# Power.net
KiCad netlist of a schematic drawn in Altium Designer
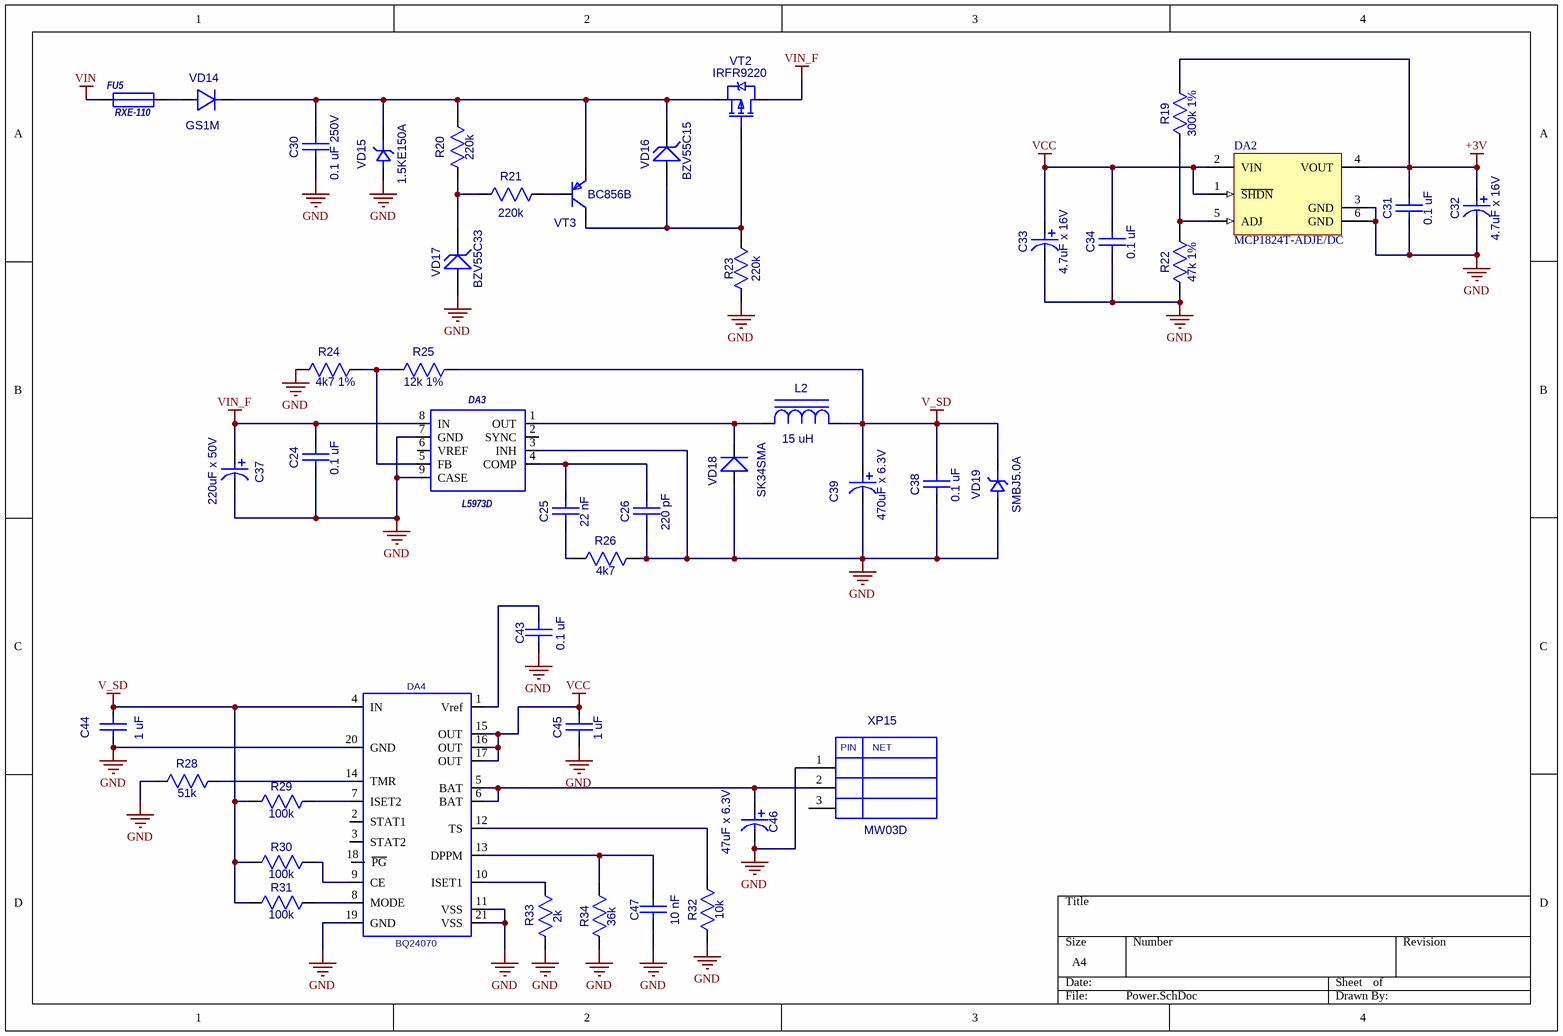
[diagram p0: Power.SchDoc]

(export (version "E")
  (design (tool "Eeschema 10.0.6"))
  (components
    (comp (ref "C24")
      (value "0.1 uF")
      (footprint "CC0603-3M")
      (description "CC0603")
      (libsource (lib "*") (part "CC0603"))
    )
    (comp (ref "C25")
      (value "22 nF")
      (footprint "CC0603-3M")
      (description "CC0603")
      (libsource (lib "*") (part "CC0603"))
    )
    (comp (ref "C26")
      (value "220 pF")
      (footprint "CC0603-3M")
      (description "CC0603")
      (libsource (lib "*") (part "CC0603"))
    )
    (comp (ref "C30")
      (value "0.1 uF 250V")
      (footprint "CC1206-MIDI")
      (description "CC1206")
      (libsource (lib "gprs_modem") (part "CC1206"))
    )
    (comp (ref "C31")
      (value "0.1 uF")
      (footprint "CC0603-3M")
      (description "CC0603")
      (libsource (lib "*") (part "CC0603"))
    )
    (comp (ref "C32")
      (value "4.7uF x 16V")
      (footprint "TAJ-A_M")
      (description "TAJ-A")
      (libsource (lib "*") (part "TAJ-A"))
    )
    (comp (ref "C33")
      (value "4.7uF x 16V")
      (footprint "TAJ-A_M")
      (description "TAJ-A")
      (libsource (lib "*") (part "TAJ-A"))
    )
    (comp (ref "C34")
      (value "0.1 uF")
      (footprint "CC0603-3M")
      (description "CC0603")
      (libsource (lib "*") (part "CC0603"))
    )
    (comp (ref "C37")
      (value "220uF x 50V")
      (footprint "CC16X10_CAP0.5(1)(Primary)")
      (description "CAP0.5(1)")
      (libsource (lib "gprs_modem") (part "CAP0.5(1)"))
    )
    (comp (ref "C38")
      (value "0.1 uF")
      (footprint "CC0603-3M")
      (description "CC0603")
      (libsource (lib "*") (part "CC0603"))
    )
    (comp (ref "C39")
      (value "470uF x 6.3V")
      (footprint "TAJ-D-1M")
      (description "TAJ-D")
      (libsource (lib "gprs_modem") (part "TAJ-D"))
    )
    (comp (ref "C43")
      (value "0.1 uF")
      (footprint "CC0603-3M")
      (description "CC0603")
      (libsource (lib "gprs_modem") (part "CC0603"))
    )
    (comp (ref "C44")
      (value "1 uF")
      (footprint "CC0603-3M")
      (description "CC0603")
      (libsource (lib "*") (part "CC0603"))
    )
    (comp (ref "C45")
      (value "1 uF")
      (footprint "CC0603-3M")
      (description "CC0603")
      (libsource (lib "*") (part "CC0603"))
    )
    (comp (ref "C46")
      (value "47uF x 6.3V")
      (footprint "TAJ-B-1M")
      (description "TAJ-B")
      (libsource (lib "*") (part "TAJ-B"))
    )
    (comp (ref "C47")
      (value "10 nF")
      (footprint "CC0603-3M")
      (description "CC0603")
      (libsource (lib "gprs_modem") (part "CC0603"))
    )
    (comp (ref "DA2")
      (value "MCP1824T-ADJE/DC")
      (footprint "SOT223-6")
      (fields (field (name "PUBLISHER") "Altium Limited"))
      (libsource (lib "gprs_modem") (part "MCP1824T-ADJE/DC"))
    )
    (comp (ref "DA3") (value "L5973D") (footprint "SO-8_EXP_PAD") (libsource (lib "*") (part "L5973D")))
    (comp (ref "DA4")
      (value "BQ24070")
      (footprint "P-PQFP-N20")
      (libsource (lib "gprs_modem") (part "BQ24070"))
    )
    (comp (ref "FU5") (value "RXE-110") (footprint "RXE-110") (libsource (lib "gprs_modem") (part "RXE-110")))
    (comp (ref "L2")
      (value "15 uH")
      (footprint "SDR0805")
      (description "SDR0805")
      (libsource (lib "*") (part "SDR0805"))
    )
    (comp (ref "R19")
      (value "300k 1%")
      (footprint "RC0603-3M")
      (description "RC0603")
      (libsource (lib "*") (part "RC0603"))
    )
    (comp (ref "R20")
      (value "220k")
      (footprint "RC1206-2M")
      (description "RC1206")
      (libsource (lib "gprs_modem") (part "RC1206"))
    )
    (comp (ref "R21")
      (value "220k")
      (footprint "RC1206-2M")
      (description "RC1206")
      (libsource (lib "gprs_modem") (part "RC1206"))
    )
    (comp (ref "R22")
      (value "47k 1%")
      (footprint "RC0603-3M")
      (description "RC0603")
      (libsource (lib "*") (part "RC0603"))
    )
    (comp (ref "R23")
      (value "220k")
      (footprint "RC1206-2M")
      (description "RC1206")
      (libsource (lib "gprs_modem") (part "RC1206"))
    )
    (comp (ref "R24")
      (value "4k7 1%")
      (footprint "RC0603-3M")
      (description "RC0603")
      (libsource (lib "*") (part "RC0603"))
    )
    (comp (ref "R25")
      (value "12k 1%")
      (footprint "RC0603-3M")
      (description "RC0603")
      (libsource (lib "*") (part "RC0603"))
    )
    (comp (ref "R26")
      (value "4k7")
      (footprint "RC0603-3M")
      (description "RC0603")
      (libsource (lib "*") (part "RC0603"))
    )
    (comp (ref "R28")
      (value "51k")
      (footprint "RC0603-3M")
      (description "RC0603")
      (libsource (lib "*") (part "RC0603"))
    )
    (comp (ref "R29")
      (value "100k")
      (footprint "RC0603-3M")
      (description "RC0603")
      (libsource (lib "*") (part "RC0603"))
    )
    (comp (ref "R30")
      (value "100k")
      (footprint "RC0603-3M")
      (description "RC0603")
      (libsource (lib "*") (part "RC0603"))
    )
    (comp (ref "R31")
      (value "100k")
      (footprint "RC0603-3M")
      (description "RC0603")
      (libsource (lib "*") (part "RC0603"))
    )
    (comp (ref "R32")
      (value "10k")
      (footprint "RC0603-3M")
      (description "RC0603")
      (libsource (lib "*") (part "RC0603"))
    )
    (comp (ref "R33")
      (value "2k")
      (footprint "RC0603-3M")
      (description "RC0603")
      (libsource (lib "*") (part "RC0603"))
    )
    (comp (ref "R34")
      (value "36k")
      (footprint "RC0603-3M")
      (description "RC0603")
      (libsource (lib "*") (part "RC0603"))
    )
    (comp (ref "VD14") (value "GS1M") (footprint "SMA") (libsource (lib "gprs_modem") (part "GS1M")))
    (comp (ref "VD15")
      (value "1.5KE150A")
      (footprint "DO-201")
      (description "1.5KE")
      (libsource (lib "gprs_modem") (part "1.5KE"))
    )
    (comp (ref "VD16")
      (value "BZV55C15")
      (footprint "SOD-80")
      (description "Zener Voltage Regulator Diode")
      (libsource (lib "gprs_modem") (part "BZV55C12"))
    )
    (comp (ref "VD17")
      (value "BZV55C33")
      (footprint "SOD-80")
      (description "Zener Voltage Regulator Diode")
      (libsource (lib "gprs_modem") (part "BZV55C12"))
    )
    (comp (ref "VD18")
      (value "SK34SMA")
      (footprint "SMA")
      (description "Schottky Rectifier")
      (libsource (lib "gprs_modem") (part "SK34SMA"))
    )
    (comp (ref "VD19")
      (value "SMBJ5.0A")
      (footprint "SMB")
      (description "SMBJ")
      (libsource (lib "gprs_modem") (part "SMBJ"))
    )
    (comp (ref "VT2")
      (value "IRFR9220")
      (footprint "D-PAK(TO-252AA)")
      (description "HEXFET Power MOSFET")
      (libsource (lib "gprs_modem") (part "IRFR9220"))
    )
    (comp (ref "VT3")
      (value "BC856B")
      (footprint "SOT-23(123)")
      (description "BC857B")
      (libsource (lib "gprs_modem") (part "BC857B"))
    )
    (comp (ref "XP15") (value "MW03D") (footprint "MW03D") (libsource (lib "gprs_modem") (part "MW03D")))
  )
  (nets
    (net (code "1") (name "+3V") (class "Default")
      (node (ref "C31") (pin "2") (pinfunction "B_2") (pintype "passive"))
      (node (ref "C32") (pin "1") (pinfunction "A_1") (pintype "passive"))
      (node (ref "DA2") (pin "4") (pinfunction "VOUT_4") (pintype "power_in"))
      (node (ref "R19") (pin "2") (pinfunction "B_2") (pintype "passive"))
    )
    (net (code "2") (name "GND") (class "Default")
      (node (ref "C24") (pin "2") (pinfunction "B_2") (pintype "passive"))
      (node (ref "C26") (pin "2") (pinfunction "B_2") (pintype "passive"))
      (node (ref "C30") (pin "2") (pinfunction "B_2") (pintype "passive"))
      (node (ref "C31") (pin "1") (pinfunction "A_1") (pintype "passive"))
      (node (ref "C32") (pin "2") (pinfunction "B_2") (pintype "passive"))
      (node (ref "C33") (pin "2") (pinfunction "B_2") (pintype "passive"))
      (node (ref "C34") (pin "1") (pinfunction "A_1") (pintype "passive"))
      (node (ref "C37") (pin "1") (pintype "passive"))
      (node (ref "C38") (pin "2") (pinfunction "B_2") (pintype "passive"))
      (node (ref "C39") (pin "2") (pinfunction "B_2") (pintype "passive"))
      (node (ref "C43") (pin "2") (pinfunction "B_2") (pintype "passive"))
      (node (ref "C44") (pin "2") (pinfunction "B_2") (pintype "passive"))
      (node (ref "C45") (pin "2") (pinfunction "B_2") (pintype "passive"))
      (node (ref "C46") (pin "2") (pinfunction "B_2") (pintype "passive"))
      (node (ref "C47") (pin "2") (pinfunction "B_2") (pintype "passive"))
      (node (ref "DA2") (pin "3") (pinfunction "GND_3") (pintype "power_in"))
      (node (ref "DA2") (pin "6") (pinfunction "GND_6") (pintype "power_in"))
      (node (ref "DA3") (pin "3") (pinfunction "INH_3") (pintype "passive"))
      (node (ref "DA3") (pin "7") (pinfunction "GND_7") (pintype "passive"))
      (node (ref "DA3") (pin "9") (pinfunction "CASE_9") (pintype "passive"))
      (node (ref "DA4") (pin "11") (pinfunction "VSS_11") (pintype "passive"))
      (node (ref "DA4") (pin "19") (pinfunction "GND_19") (pintype "passive"))
      (node (ref "DA4") (pin "20") (pinfunction "GND_20") (pintype "passive"))
      (node (ref "DA4") (pin "21") (pinfunction "VSS_21") (pintype "passive"))
      (node (ref "R22") (pin "1") (pinfunction "A_1") (pintype "passive"))
      (node (ref "R23") (pin "2") (pinfunction "B_2") (pintype "passive"))
      (node (ref "R24") (pin "1") (pinfunction "A_1") (pintype "passive"))
      (node (ref "R26") (pin "2") (pinfunction "B_2") (pintype "passive"))
      (node (ref "R28") (pin "1") (pinfunction "A_1") (pintype "passive"))
      (node (ref "R32") (pin "1") (pinfunction "A_1") (pintype "passive"))
      (node (ref "R33") (pin "1") (pinfunction "A_1") (pintype "passive"))
      (node (ref "R34") (pin "1") (pinfunction "A_1") (pintype "passive"))
      (node (ref "VD15") (pin "1") (pinfunction "A_1") (pintype "passive"))
      (node (ref "VD17") (pin "1") (pinfunction "A_1") (pintype "passive"))
      (node (ref "VD18") (pin "1") (pinfunction "A_1") (pintype "passive"))
      (node (ref "VD19") (pin "1") (pinfunction "A_1") (pintype "passive"))
      (node (ref "XP15") (pin "1") (pinfunction "1_1") (pintype "passive"))
    )
    (net (code "3") (name "Net-(C25-A)") (class "Default")
      (node (ref "C25") (pin "1") (pinfunction "A_1") (pintype "passive"))
      (node (ref "C26") (pin "1") (pinfunction "A_1") (pintype "passive"))
      (node (ref "DA3") (pin "4") (pinfunction "COMP_4") (pintype "passive"))
    )
    (net (code "4") (name "Net-(C25-B)") (class "Default")
      (node (ref "C25") (pin "2") (pinfunction "B_2") (pintype "passive"))
      (node (ref "R26") (pin "1") (pinfunction "A_1") (pintype "passive"))
    )
    (net (code "5") (name "Net-(C30-A)") (class "Default")
      (node (ref "C30") (pin "1") (pinfunction "A_1") (pintype "passive"))
      (node (ref "R20") (pin "2") (pinfunction "B_2") (pintype "passive"))
      (node (ref "VD14") (pin "2") (pinfunction "K_2") (pintype "passive"))
      (node (ref "VD15") (pin "2") (pinfunction "K_2") (pintype "passive"))
      (node (ref "VD16") (pin "2") (pintype "passive"))
      (node (ref "VT2") (pin "2") (pinfunction "S_2") (pintype "passive"))
      (node (ref "VT3") (pin "2") (pinfunction "E_2") (pintype "passive"))
    )
    (net (code "6") (name "Net-(C43-A)") (class "Default")
      (node (ref "C43") (pin "1") (pinfunction "A_1") (pintype "passive"))
      (node (ref "DA4") (pin "1") (pinfunction "Vref_1") (pintype "passive"))
    )
    (net (code "7") (name "Net-(C46-A)") (class "Default")
      (node (ref "C46") (pin "1") (pinfunction "A_1") (pintype "passive"))
      (node (ref "DA4") (pin "5") (pinfunction "BAT_5") (pintype "passive"))
      (node (ref "DA4") (pin "6") (pinfunction "BAT_6") (pintype "passive"))
      (node (ref "XP15") (pin "2") (pinfunction "2_2") (pintype "passive"))
    )
    (net (code "8") (name "Net-(C47-A)") (class "Default")
      (node (ref "C47") (pin "1") (pinfunction "A_1") (pintype "passive"))
      (node (ref "DA4") (pin "13") (pinfunction "DPPM_13") (pintype "passive"))
      (node (ref "R34") (pin "2") (pinfunction "B_2") (pintype "passive"))
    )
    (net (code "9") (name "Net-(DA2-ADJ)") (class "Default")
      (node (ref "DA2") (pin "5") (pinfunction "ADJ_5") (pintype "input"))
      (node (ref "R19") (pin "1") (pinfunction "A_1") (pintype "passive"))
      (node (ref "R22") (pin "2") (pinfunction "B_2") (pintype "passive"))
    )
    (net (code "10") (name "Net-(DA3-FB)") (class "Default")
      (node (ref "DA3") (pin "5") (pinfunction "FB_5") (pintype "passive"))
      (node (ref "R24") (pin "2") (pinfunction "B_2") (pintype "passive"))
      (node (ref "R25") (pin "1") (pinfunction "A_1") (pintype "passive"))
    )
    (net (code "11") (name "Net-(DA3-OUT)") (class "Default")
      (node (ref "DA3") (pin "1") (pinfunction "OUT_1") (pintype "passive"))
      (node (ref "L2") (pin "1") (pinfunction "C_1") (pintype "passive"))
      (node (ref "VD18") (pin "2") (pinfunction "K_2") (pintype "passive"))
    )
    (net (code "12") (name "Net-(DA4-CE)") (class "Default")
      (node (ref "DA4") (pin "9") (pinfunction "CE_9") (pintype "passive"))
      (node (ref "R30") (pin "2") (pinfunction "B_2") (pintype "passive"))
    )
    (net (code "13") (name "Net-(DA4-ISET1)") (class "Default")
      (node (ref "DA4") (pin "10") (pinfunction "ISET1_10") (pintype "passive"))
      (node (ref "R33") (pin "2") (pinfunction "B_2") (pintype "passive"))
    )
    (net (code "14") (name "Net-(DA4-ISET2)") (class "Default")
      (node (ref "DA4") (pin "7") (pinfunction "ISET2_7") (pintype "passive"))
      (node (ref "R29") (pin "2") (pinfunction "B_2") (pintype "passive"))
    )
    (net (code "15") (name "Net-(DA4-MODE)") (class "Default")
      (node (ref "DA4") (pin "8") (pinfunction "MODE_8") (pintype "passive"))
      (node (ref "R31") (pin "2") (pinfunction "B_2") (pintype "passive"))
    )
    (net (code "16") (name "Net-(DA4-TMR)") (class "Default")
      (node (ref "DA4") (pin "14") (pinfunction "TMR_14") (pintype "passive"))
      (node (ref "R28") (pin "2") (pinfunction "B_2") (pintype "passive"))
    )
    (net (code "17") (name "Net-(DA4-TS)") (class "Default")
      (node (ref "DA4") (pin "12") (pinfunction "TS_12") (pintype "passive"))
      (node (ref "R32") (pin "2") (pinfunction "B_2") (pintype "passive"))
    )
    (net (code "18") (name "Net-(R20-A)") (class "Default")
      (node (ref "R20") (pin "1") (pinfunction "A_1") (pintype "passive"))
      (node (ref "R21") (pin "1") (pinfunction "A_1") (pintype "passive"))
      (node (ref "VD17") (pin "2") (pintype "passive"))
    )
    (net (code "19") (name "Net-(R21-B)") (class "Default")
      (node (ref "R21") (pin "2") (pinfunction "B_2") (pintype "passive"))
      (node (ref "VT3") (pin "1") (pinfunction "B_1") (pintype "passive"))
    )
    (net (code "20") (name "Net-(R23-A)") (class "Default")
      (node (ref "R23") (pin "1") (pinfunction "A_1") (pintype "passive"))
      (node (ref "VD16") (pin "1") (pinfunction "A_1") (pintype "passive"))
      (node (ref "VT2") (pin "1") (pinfunction "G_1") (pintype "passive"))
      (node (ref "VT3") (pin "3") (pinfunction "C_3") (pintype "passive"))
    )
    (net (code "21") (name "Net-(VD14-A)") (class "Default")
      (node (ref "FU5") (pin "2") (pintype "passive"))
      (node (ref "VD14") (pin "1") (pinfunction "A_1") (pintype "passive"))
    )
    (net (code "22") (name "VCC") (class "Default")
      (node (ref "C33") (pin "1") (pinfunction "A_1") (pintype "passive"))
      (node (ref "C34") (pin "2") (pinfunction "B_2") (pintype "passive"))
      (node (ref "C45") (pin "1") (pinfunction "A_1") (pintype "passive"))
      (node (ref "DA2") (pin "1") (pinfunction "~{SHDN}_1") (pintype "input"))
      (node (ref "DA2") (pin "2") (pinfunction "VIN_2") (pintype "power_in"))
      (node (ref "DA4") (pin "15") (pinfunction "OUT_15") (pintype "passive"))
      (node (ref "DA4") (pin "16") (pinfunction "OUT_16") (pintype "passive"))
      (node (ref "DA4") (pin "17") (pinfunction "OUT_17") (pintype "passive"))
    )
    (net (code "23") (name "VIN") (class "Default") (node (ref "FU5") (pin "1") (pintype "passive")))
    (net (code "24") (name "VIN_F") (class "Default")
      (node (ref "C24") (pin "1") (pinfunction "A_1") (pintype "passive"))
      (node (ref "C37") (pin "2") (pintype "passive"))
      (node (ref "DA3") (pin "8") (pinfunction "IN_8") (pintype "passive"))
      (node (ref "VT2") (pin "3") (pinfunction "D_3") (pintype "passive"))
    )
    (net (code "25") (name "V_SD") (class "Default")
      (node (ref "C38") (pin "1") (pinfunction "A_1") (pintype "passive"))
      (node (ref "C39") (pin "1") (pinfunction "A_1") (pintype "passive"))
      (node (ref "C44") (pin "1") (pinfunction "A_1") (pintype "passive"))
      (node (ref "DA4") (pin "4") (pinfunction "IN_4") (pintype "passive"))
      (node (ref "L2") (pin "2") (pinfunction "A_2") (pintype "passive"))
      (node (ref "R25") (pin "2") (pinfunction "B_2") (pintype "passive"))
      (node (ref "R29") (pin "1") (pinfunction "A_1") (pintype "passive"))
      (node (ref "R30") (pin "1") (pinfunction "A_1") (pintype "passive"))
      (node (ref "R31") (pin "1") (pinfunction "A_1") (pintype "passive"))
      (node (ref "VD19") (pin "2") (pinfunction "K_2") (pintype "passive"))
    )
    (net (code "26") (name "unconnected-(DA3-SYNC-Pad2)") (class "Default")
      (node (ref "DA3") (pin "2") (pinfunction "SYNC_2") (pintype "passive"))
    )
    (net (code "27") (name "unconnected-(DA3-VREF-Pad6)") (class "Default")
      (node (ref "DA3") (pin "6") (pinfunction "VREF_6") (pintype "passive"))
    )
    (net (code "28") (name "unconnected-(DA4-STAT1-Pad2)") (class "Default")
      (node (ref "DA4") (pin "2") (pinfunction "STAT1_2") (pintype "passive"))
    )
    (net (code "29") (name "unconnected-(DA4-STAT2-Pad3)") (class "Default")
      (node (ref "DA4") (pin "3") (pinfunction "STAT2_3") (pintype "passive"))
    )
    (net (code "30") (name "unconnected-(DA4-~{PG}-Pad18)") (class "Default")
      (node (ref "DA4") (pin "18") (pinfunction "~{PG}_18") (pintype "passive"))
    )
    (net (code "31") (name "unconnected-(XP15-Pad3)") (class "Default")
      (node (ref "XP15") (pin "3") (pinfunction "3_3") (pintype "passive"))
    )
  )
)
